# GTM_MCUcontrolledLEDs.net
KiCad netlist of a schematic drawn in Altium Designer
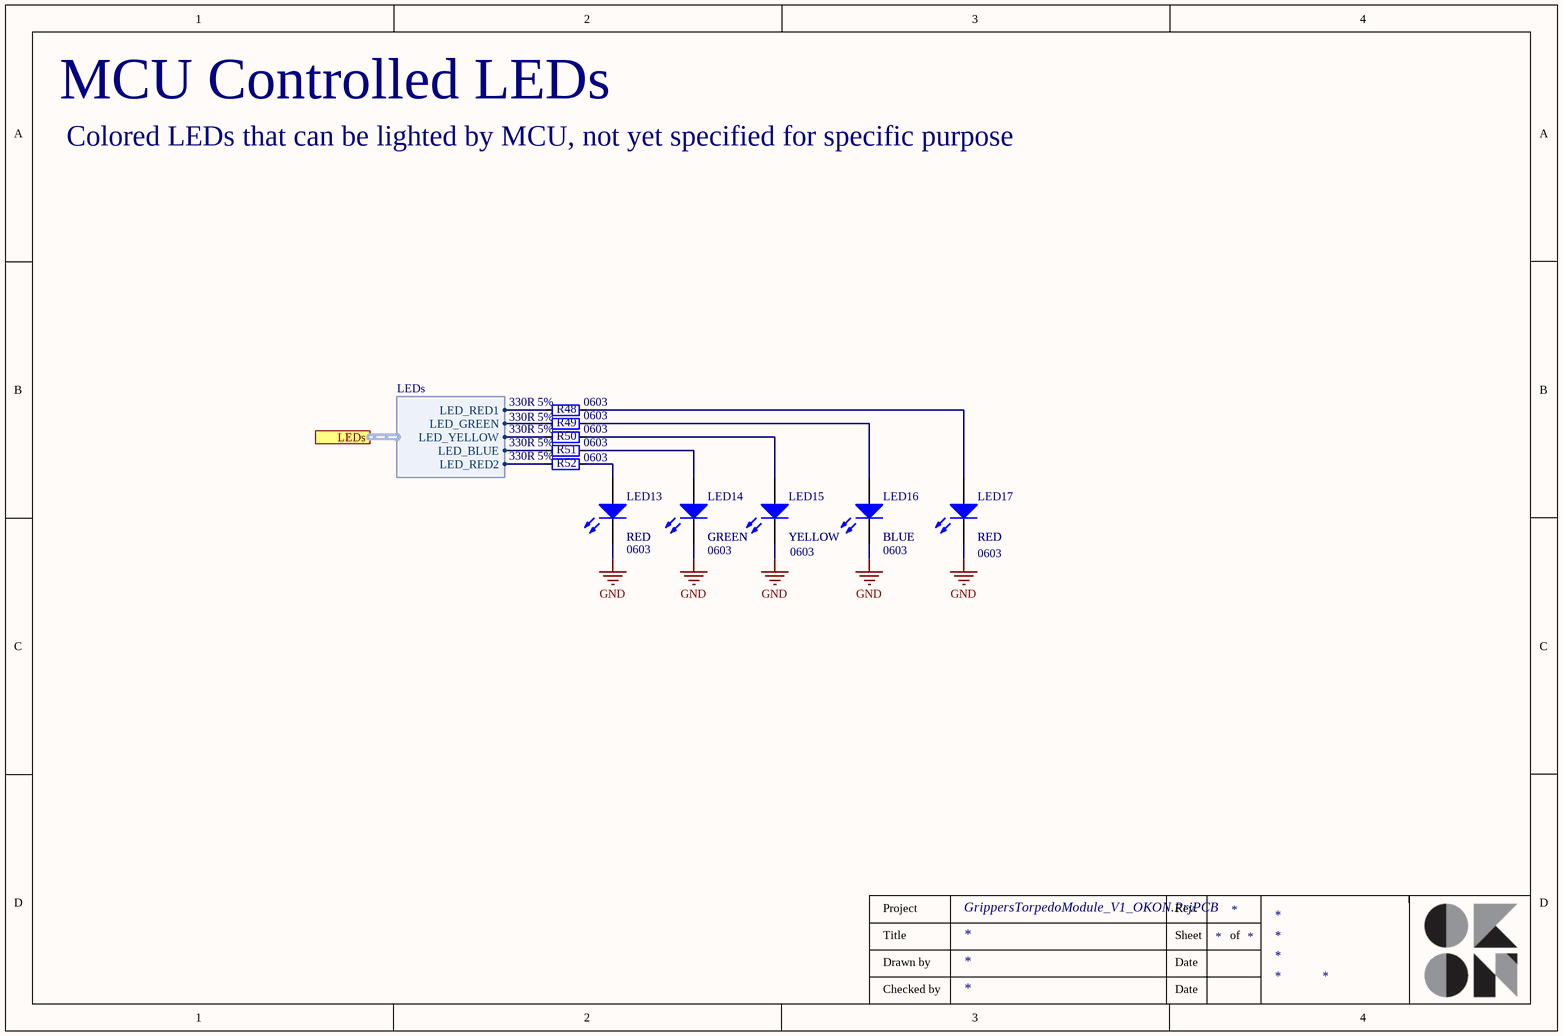
[diagram p0: GTM_MCUcontrolledLEDs.SchDoc]

(export (version "E")
  (design (tool "Eeschema 10.0.6"))
  (components
    (comp (ref "LED13")
      (value "RED")
      (footprint "LED_THT_RED")
      (description "Light-emitting diode")
      (fields (field (name "COLOR") "RED") (field (name "PACKAGE") "0603"))
      (libsource (lib "Library_Altium_KNR") (part "LED"))
    )
    (comp (ref "LED14")
      (value "GREEN")
      (footprint "LED_THT_YELLOW")
      (description "Light-emitting diode")
      (fields (field (name "COLOR") "GREEN") (field (name "PACKAGE") "0603"))
      (libsource (lib "Library_Altium_KNR") (part "LED"))
    )
    (comp (ref "LED15")
      (value "YELLOW")
      (footprint "LED_THT_GREEN")
      (description "Light-emitting diode")
      (fields (field (name "COLOR") "YELLOW") (field (name "PACKAGE") "0603"))
      (libsource (lib "Library_Altium_KNR") (part "LED"))
    )
    (comp (ref "LED16")
      (value "BLUE")
      (footprint "LED_THT_BLUE")
      (description "Light-emitting diode")
      (fields (field (name "COLOR") "BLUE") (field (name "PACKAGE") "0603"))
      (libsource (lib "Library_Altium_KNR") (part "LED"))
    )
    (comp (ref "LED17")
      (value "RED")
      (footprint "LED_THT_RED")
      (description "Light-emitting diode")
      (fields (field (name "COLOR") "RED") (field (name "PACKAGE") "0603"))
      (libsource (lib "Library_Altium_KNR") (part "LED"))
    )
    (comp (ref "R48")
      (value "330R")
      (footprint "0603")
      (description "Resistior")
      (fields (field (name "TOLERANCE") "5%") (field (name "PACKAGE") "0603"))
      (libsource (lib "Library_Altium_KNR") (part "RES"))
    )
    (comp (ref "R49")
      (value "330R")
      (footprint "0603")
      (description "Resistior")
      (fields (field (name "TOLERANCE") "5%") (field (name "PACKAGE") "0603"))
      (libsource (lib "Library_Altium_KNR") (part "RES"))
    )
    (comp (ref "R50")
      (value "330R")
      (footprint "0603")
      (description "Resistior")
      (fields (field (name "TOLERANCE") "5%") (field (name "PACKAGE") "0603"))
      (libsource (lib "Library_Altium_KNR") (part "RES"))
    )
    (comp (ref "R51")
      (value "330R")
      (footprint "0603")
      (description "Resistior")
      (fields (field (name "TOLERANCE") "5%") (field (name "PACKAGE") "0603"))
      (libsource (lib "Library_Altium_KNR") (part "RES"))
    )
    (comp (ref "R52")
      (value "330R")
      (footprint "0603")
      (description "Resistior")
      (fields (field (name "TOLERANCE") "5%") (field (name "PACKAGE") "0603"))
      (libsource (lib "Library_Altium_KNR") (part "RES"))
    )
  )
  (nets
    (net (code "2") (name "/LED_BLUE") (class "Default")
      (node (ref "R51") (pin "1") (pinfunction "1_1") (pintype "passive"))
    )
    (net (code "3") (name "/LED_GREEN") (class "Default")
      (node (ref "R49") (pin "1") (pinfunction "1_1") (pintype "passive"))
    )
    (net (code "4") (name "/LED_RED1") (class "Default")
      (node (ref "R48") (pin "1") (pinfunction "1_1") (pintype "passive"))
    )
    (net (code "5") (name "/LED_RED2") (class "Default")
      (node (ref "R52") (pin "1") (pinfunction "1_1") (pintype "passive"))
    )
    (net (code "6") (name "/LED_YELLOW") (class "Default")
      (node (ref "R50") (pin "1") (pinfunction "1_1") (pintype "passive"))
    )
    (net (code "8") (name "GND") (class "Default")
      (node (ref "LED13") (pin "2") (pinfunction "K_2") (pintype "passive"))
      (node (ref "LED14") (pin "2") (pinfunction "K_2") (pintype "passive"))
      (node (ref "LED15") (pin "2") (pinfunction "K_2") (pintype "passive"))
      (node (ref "LED16") (pin "2") (pinfunction "K_2") (pintype "passive"))
      (node (ref "LED17") (pin "2") (pinfunction "K_2") (pintype "passive"))
    )
    (net (code "9") (name "Net-(LED13-A)") (class "Default")
      (node (ref "LED13") (pin "1") (pinfunction "A_1") (pintype "passive"))
      (node (ref "R52") (pin "2") (pinfunction "2_2") (pintype "passive"))
    )
    (net (code "10") (name "Net-(LED14-A)") (class "Default")
      (node (ref "LED14") (pin "1") (pinfunction "A_1") (pintype "passive"))
      (node (ref "R51") (pin "2") (pinfunction "2_2") (pintype "passive"))
    )
    (net (code "11") (name "Net-(LED15-A)") (class "Default")
      (node (ref "LED15") (pin "1") (pinfunction "A_1") (pintype "passive"))
      (node (ref "R50") (pin "2") (pinfunction "2_2") (pintype "passive"))
    )
    (net (code "12") (name "Net-(LED16-A)") (class "Default")
      (node (ref "LED16") (pin "1") (pinfunction "A_1") (pintype "passive"))
      (node (ref "R49") (pin "2") (pinfunction "2_2") (pintype "passive"))
    )
    (net (code "13") (name "Net-(LED17-A)") (class "Default")
      (node (ref "LED17") (pin "1") (pinfunction "A_1") (pintype "passive"))
      (node (ref "R48") (pin "2") (pinfunction "2_2") (pintype "passive"))
    )
  )
)
